# 4H-LedLight.net
KiCad netlist of a schematic drawn in EAGLE
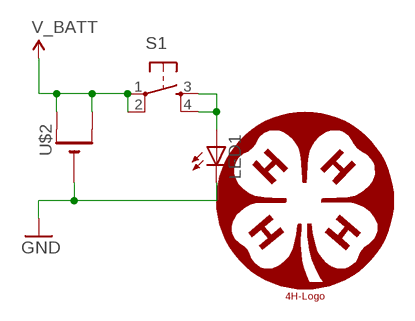
[diagram p0: schematic, sheet 1]

(export (version "E")
  (design (tool "Eeschema 10.0.6"))
  (components
    (comp (ref "LED1")
      (value "LEDOVAL")
      (footprint "eagle-import:LED-OVAL")
      (libsource (lib "eagle-import") (part "LEDOVAL"))
    )
    (comp (ref "S1")
      (value "TAC_SWITCHPTH")
      (footprint "eagle-import:TACTILE-PTH")
      (libsource (lib "eagle-import") (part "TAC_SWITCHPTH"))
    )
    (comp (ref "U$1")
      (value "4H-LOGO6")
      (footprint "eagle-import:4H_LOGO_6")
      (libsource (lib "eagle-import") (part "4H-LOGO6"))
    )
    (comp (ref "U$2")
      (value "CR2032THM")
      (footprint "eagle-import:CR2032-THRU")
      (libsource (lib "eagle-import") (part "CR2032THM"))
    )
  )
  (nets
    (net (code "1") (name "GND") (class "Default")
      (node (ref "LED1") (pin "CATHODE") (pinfunction "C_CATHODE") (pintype "passive"))
      (node (ref "U$2") (pin "-") (pinfunction "-_-") (pintype "passive"))
    )
    (net (code "2") (name "Net-(LED1-A)") (class "Default")
      (node (ref "LED1") (pin "ANODE") (pinfunction "A_ANODE") (pintype "passive"))
      (node (ref "S1") (pin "3") (pinfunction "3_3") (pintype "passive"))
      (node (ref "S1") (pin "4") (pinfunction "4_4") (pintype "passive"))
    )
    (net (code "3") (name "V_BATT") (class "Default")
      (node (ref "S1") (pin "1") (pinfunction "1_1") (pintype "passive"))
      (node (ref "S1") (pin "2") (pinfunction "2_2") (pintype "passive"))
      (node (ref "U$2") (pin "+1") (pinfunction "+_+1") (pintype "passive"))
      (node (ref "U$2") (pin "+2") (pinfunction "+1_+2") (pintype "passive"))
    )
  )
)
